# thtV1_0.net
KiCad netlist of a schematic drawn in EAGLE
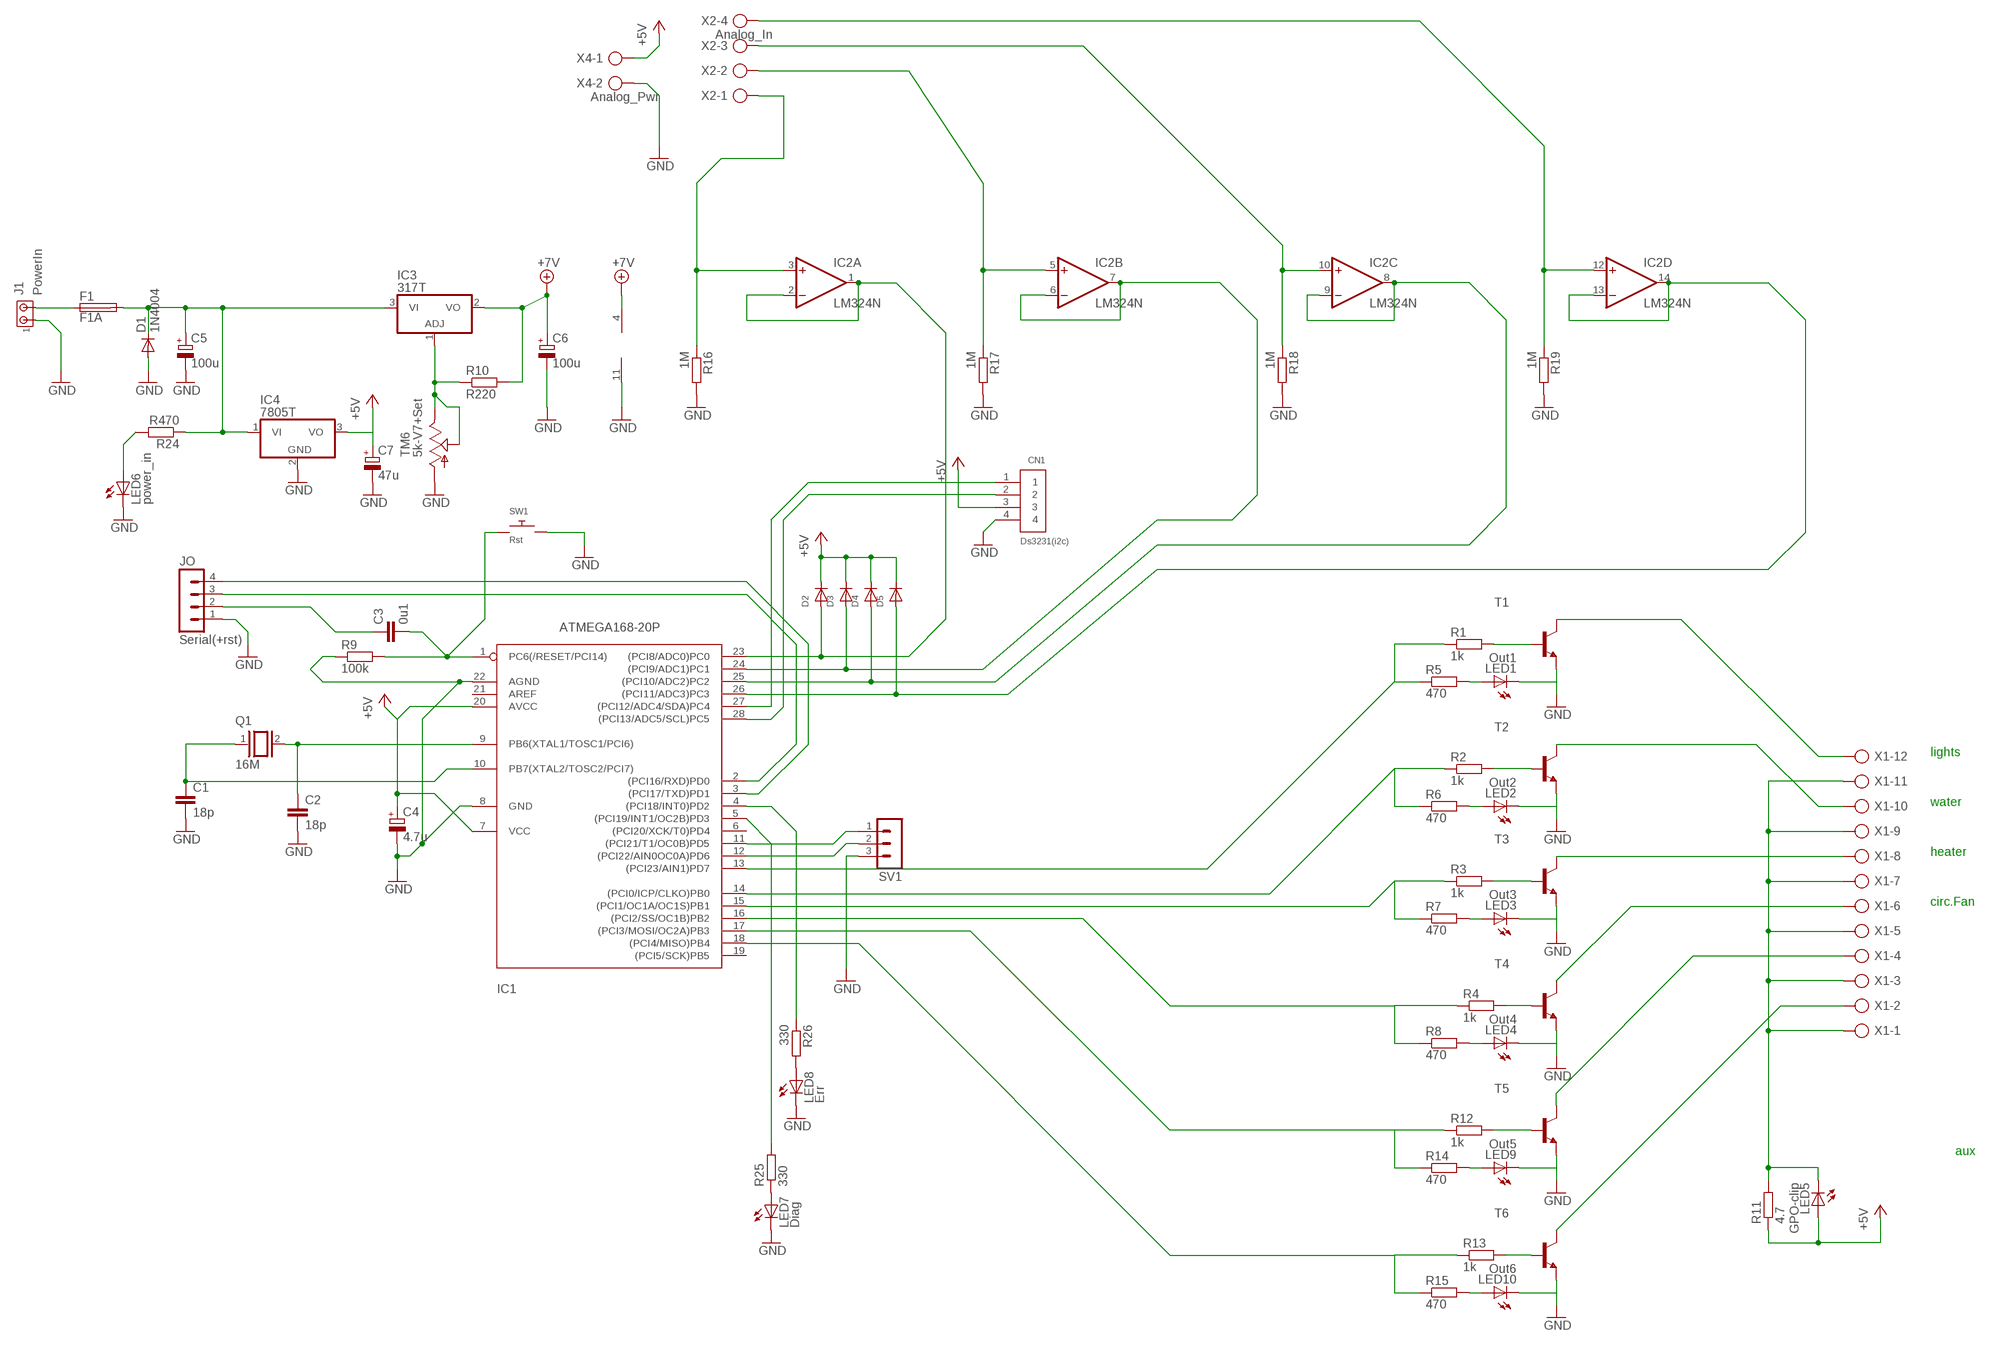
[diagram p0: schematic, sheet 1]

(export (version "E")
  (design (tool "Eeschema 10.0.6"))
  (components
    (comp (ref "C1")
      (value "18p")
      (footprint "eagle-import:C025-024X044")
      (libsource (lib "eagle-import") (part "C-EU025-024X044"))
    )
    (comp (ref "C2")
      (value "18p")
      (footprint "eagle-import:C025-024X044")
      (libsource (lib "eagle-import") (part "C-EU025-024X044"))
    )
    (comp (ref "C3")
      (value "0u1")
      (footprint "eagle-import:C050-030X075")
      (libsource (lib "eagle-import") (part "C-EU050-030X075"))
    )
    (comp (ref "C4")
      (value "4.7u")
      (footprint "eagle-import:E5-10,5")
      (libsource (lib "eagle-import") (part "CPOL-EUE5-10.5"))
    )
    (comp (ref "C5")
      (value "100u")
      (footprint "eagle-import:E5-10,5")
      (libsource (lib "eagle-import") (part "CPOL-EUE5-10.5"))
    )
    (comp (ref "C6")
      (value "100u")
      (footprint "eagle-import:E3,5-8")
      (libsource (lib "eagle-import") (part "CPOL-EUE3.5-8"))
    )
    (comp (ref "C7")
      (value "47u")
      (footprint "eagle-import:E2,5-6E")
      (libsource (lib "eagle-import") (part "CPOL-EUE2,5-6E"))
    )
    (comp (ref "CN1")
      (value "Ds3231(i2c)")
      (footprint "eagle-import:1X04-BIG")
      (libsource (lib "eagle-import") (part "1X4-BIG"))
    )
    (comp (ref "D1")
      (value "1N4004")
      (footprint "eagle-import:DO41-10")
      (libsource (lib "eagle-import") (part "1N4004"))
    )
    (comp (ref "D2")
      (value "DIODEDO-1N4148")
      (footprint "eagle-import:DO-1N4148")
      (libsource (lib "eagle-import") (part "DIODEDO-1N4148"))
    )
    (comp (ref "D3")
      (value "DIODEDO-1N4148")
      (footprint "eagle-import:DO-1N4148")
      (libsource (lib "eagle-import") (part "DIODEDO-1N4148"))
    )
    (comp (ref "D4")
      (value "DIODEDO-1N4148")
      (footprint "eagle-import:DO-1N4148")
      (libsource (lib "eagle-import") (part "DIODEDO-1N4148"))
    )
    (comp (ref "D5")
      (value "DIODEDO-1N4148")
      (footprint "eagle-import:DO-1N4148")
      (libsource (lib "eagle-import") (part "DIODEDO-1N4148"))
    )
    (comp (ref "F1")
      (value "F1A")
      (footprint "eagle-import:GSH15")
      (fields (field (name "MPN") "64900001039"))
      (libsource (lib "eagle-import") (part "GSH15"))
    )
    (comp (ref "IC1")
      (value "ATMEGA168-20P")
      (footprint "eagle-import:DIL28-3")
      (libsource (lib "eagle-import") (part "ATMEGA168P-20"))
    )
    (comp (ref "IC2")
      (value "LM324N")
      (footprint "eagle-import:DIL14")
      (libsource (lib "eagle-import") (part "LM324N"))
    )
    (comp (ref "IC3")
      (value "317T")
      (footprint "eagle-import:TO220H")
      (libsource (lib "eagle-import") (part "317T"))
    )
    (comp (ref "IC4")
      (value "7805T")
      (footprint "eagle-import:TO220H")
      (libsource (lib "eagle-import") (part "78T05"))
    )
    (comp (ref "J1")
      (value "PowerIn")
      (footprint "eagle-import:1X2MTA")
      (libsource (lib "eagle-import") (part "MTA02-156"))
    )
    (comp (ref "JO")
      (value "Serial(+rst)")
      (footprint "eagle-import:MA04-1")
      (libsource (lib "eagle-import") (part "MA04-1"))
    )
    (comp (ref "LED1")
      (value "Out1")
      (footprint "eagle-import:LED3MM")
      (libsource (lib "eagle-import") (part "LED3MM"))
    )
    (comp (ref "LED2")
      (value "Out2")
      (footprint "eagle-import:LED3MM")
      (libsource (lib "eagle-import") (part "LED3MM"))
    )
    (comp (ref "LED3")
      (value "Out3")
      (footprint "eagle-import:LED3MM")
      (libsource (lib "eagle-import") (part "LED3MM"))
    )
    (comp (ref "LED4")
      (value "Out4")
      (footprint "eagle-import:LED3MM")
      (libsource (lib "eagle-import") (part "LED3MM"))
    )
    (comp (ref "LED5")
      (value "GPO-clip")
      (footprint "eagle-import:LED3MM")
      (libsource (lib "eagle-import") (part "LED3MM"))
    )
    (comp (ref "LED6")
      (value "power_in")
      (footprint "eagle-import:LED3MM")
      (libsource (lib "eagle-import") (part "LED3MM"))
    )
    (comp (ref "LED7")
      (value "Diag")
      (footprint "eagle-import:LED3MM")
      (libsource (lib "eagle-import") (part "LED3MM"))
    )
    (comp (ref "LED8")
      (value "Err")
      (footprint "eagle-import:LED3MM")
      (libsource (lib "eagle-import") (part "LED3MM"))
    )
    (comp (ref "LED9")
      (value "Out5")
      (footprint "eagle-import:LED3MM")
      (libsource (lib "eagle-import") (part "LED3MM"))
    )
    (comp (ref "LED10")
      (value "Out6")
      (footprint "eagle-import:LED3MM")
      (libsource (lib "eagle-import") (part "LED3MM"))
    )
    (comp (ref "Q1")
      (value "16M")
      (footprint "eagle-import:QS")
      (libsource (lib "eagle-import") (part "XTAL/S"))
    )
    (comp (ref "R1")
      (value "1k")
      (footprint "eagle-import:0207_10")
      (libsource (lib "eagle-import") (part "R-EU_0207/10"))
    )
    (comp (ref "R2")
      (value "1k")
      (footprint "eagle-import:0207_10")
      (libsource (lib "eagle-import") (part "R-EU_0207/10"))
    )
    (comp (ref "R3")
      (value "1k")
      (footprint "eagle-import:0207_10")
      (libsource (lib "eagle-import") (part "R-EU_0207/10"))
    )
    (comp (ref "R4")
      (value "1k")
      (footprint "eagle-import:0207_10")
      (libsource (lib "eagle-import") (part "R-EU_0207/10"))
    )
    (comp (ref "R5")
      (value "470")
      (footprint "eagle-import:0204V")
      (libsource (lib "eagle-import") (part "R-EU_0204/2V"))
    )
    (comp (ref "R6")
      (value "470")
      (footprint "eagle-import:0204V")
      (libsource (lib "eagle-import") (part "R-EU_0204/2V"))
    )
    (comp (ref "R7")
      (value "470")
      (footprint "eagle-import:0204V")
      (libsource (lib "eagle-import") (part "R-EU_0204/2V"))
    )
    (comp (ref "R8")
      (value "470")
      (footprint "eagle-import:0204V")
      (libsource (lib "eagle-import") (part "R-EU_0204/2V"))
    )
    (comp (ref "R9")
      (value "100k")
      (footprint "eagle-import:0207_10")
      (libsource (lib "eagle-import") (part "R-EU_0207/10"))
    )
    (comp (ref "R10")
      (value "R220")
      (footprint "eagle-import:0207_10")
      (libsource (lib "eagle-import") (part "R-EU_0207/10"))
    )
    (comp (ref "R11")
      (value "4.7")
      (footprint "eagle-import:0207_10")
      (libsource (lib "eagle-import") (part "R-EU_0207/10"))
    )
    (comp (ref "R12")
      (value "1k")
      (footprint "eagle-import:0207_10")
      (libsource (lib "eagle-import") (part "R-EU_0207/10"))
    )
    (comp (ref "R13")
      (value "1k")
      (footprint "eagle-import:0207_10")
      (libsource (lib "eagle-import") (part "R-EU_0207/10"))
    )
    (comp (ref "R14")
      (value "470")
      (footprint "eagle-import:0204V")
      (libsource (lib "eagle-import") (part "R-EU_0204/2V"))
    )
    (comp (ref "R15")
      (value "470")
      (footprint "eagle-import:0204V")
      (libsource (lib "eagle-import") (part "R-EU_0204/2V"))
    )
    (comp (ref "R16")
      (value "1M")
      (footprint "eagle-import:0204V")
      (libsource (lib "eagle-import") (part "R-EU_0204/2V"))
    )
    (comp (ref "R17")
      (value "1M")
      (footprint "eagle-import:0204V")
      (libsource (lib "eagle-import") (part "R-EU_0204/2V"))
    )
    (comp (ref "R18")
      (value "1M")
      (footprint "eagle-import:0204V")
      (libsource (lib "eagle-import") (part "R-EU_0204/2V"))
    )
    (comp (ref "R19")
      (value "1M")
      (footprint "eagle-import:0204V")
      (libsource (lib "eagle-import") (part "R-EU_0204/2V"))
    )
    (comp (ref "R24")
      (value "R470")
      (footprint "eagle-import:0207_10")
      (libsource (lib "eagle-import") (part "R-EU_0207/10"))
    )
    (comp (ref "R25")
      (value "330")
      (footprint "eagle-import:0207_2V")
      (libsource (lib "eagle-import") (part "R-EU_0207/2V"))
    )
    (comp (ref "R26")
      (value "330")
      (footprint "eagle-import:0207_2V")
      (libsource (lib "eagle-import") (part "R-EU_0207/2V"))
    )
    (comp (ref "SV1")
      (value "MA03-1")
      (footprint "eagle-import:MA03-1")
      (libsource (lib "eagle-import") (part "MA03-1"))
    )
    (comp (ref "SW1")
      (value "Rst")
      (footprint "eagle-import:TACT_PANA-EVQ")
      (libsource (lib "eagle-import") (part "SWITCH_PUSHBUTTONEVQ-PE"))
    )
    (comp (ref "T1")
      (value "BC547A-NPN-TO92-CBE")
      (footprint "eagle-import:TO92-CBE")
      (libsource (lib "eagle-import") (part "-NPN-TO92-CBEBC547A"))
    )
    (comp (ref "T2")
      (value "BC547A-NPN-TO92-CBE")
      (footprint "eagle-import:TO92-CBE")
      (libsource (lib "eagle-import") (part "-NPN-TO92-CBEBC547A"))
    )
    (comp (ref "T3")
      (value "BC547A-NPN-TO92-CBE")
      (footprint "eagle-import:TO92-CBE")
      (libsource (lib "eagle-import") (part "-NPN-TO92-CBEBC547A"))
    )
    (comp (ref "T4")
      (value "BC547A-NPN-TO92-CBE")
      (footprint "eagle-import:TO92-CBE")
      (libsource (lib "eagle-import") (part "-NPN-TO92-CBEBC547A"))
    )
    (comp (ref "T5")
      (value "BC547A-NPN-TO92-CBE")
      (footprint "eagle-import:TO92-CBE")
      (libsource (lib "eagle-import") (part "-NPN-TO92-CBEBC547A"))
    )
    (comp (ref "T6")
      (value "BC547A-NPN-TO92-CBE")
      (footprint "eagle-import:TO92-CBE")
      (libsource (lib "eagle-import") (part "-NPN-TO92-CBEBC547A"))
    )
    (comp (ref "TM6")
      (value "5k-V7+Set")
      (footprint "eagle-import:6MM")
      (libsource (lib "eagle-import") (part "TRIM"))
    )
    (comp (ref "X1")
      (value "AK300/12")
      (footprint "eagle-import:AK300_12")
      (libsource (lib "eagle-import") (part "AK300/12"))
    )
    (comp (ref "X2")
      (value "Analog_In")
      (footprint "eagle-import:AK300_4")
      (libsource (lib "eagle-import") (part "AK300/4"))
    )
    (comp (ref "X4")
      (value "Analog_Pwr")
      (footprint "eagle-import:AK300_2")
      (libsource (lib "eagle-import") (part "AK300/2"))
    )
  )
  (nets
    (net (code "1") (name "+5V") (class "Default")
      (node (ref "C4") (pin "+") (pinfunction "+_+") (pintype "passive"))
      (node (ref "C7") (pin "+") (pinfunction "+_+") (pintype "passive"))
      (node (ref "CN1") (pin "3") (pinfunction "3_3") (pintype "bidirectional"))
      (node (ref "D2") (pin "C") (pinfunction "C_C") (pintype "passive"))
      (node (ref "D3") (pin "C") (pinfunction "C_C") (pintype "passive"))
      (node (ref "D4") (pin "C") (pinfunction "C_C") (pintype "passive"))
      (node (ref "D5") (pin "C") (pinfunction "C_C") (pintype "passive"))
      (node (ref "IC1") (pin "20") (pinfunction "AVCC_20") (pintype "bidirectional"))
      (node (ref "IC1") (pin "7") (pinfunction "VCC_7") (pintype "bidirectional"))
      (node (ref "IC4") (pin "3") (pinfunction "VO_3") (pintype "passive"))
      (node (ref "LED5") (pin "A") (pinfunction "A_A") (pintype "passive"))
      (node (ref "R11") (pin "1") (pinfunction "1_1") (pintype "passive"))
      (node (ref "X4") (pin "1") (pinfunction "KL_1") (pintype "passive"))
    )
    (net (code "2") (name "+7V") (class "Default")
      (node (ref "C6") (pin "+") (pinfunction "+_+") (pintype "passive"))
      (node (ref "IC2") (pin "4") (pinfunction "V+_4") (pintype "power_in"))
      (node (ref "IC3") (pin "2") (pinfunction "VO_2") (pintype "passive"))
      (node (ref "R10") (pin "2") (pinfunction "2_2") (pintype "passive"))
    )
    (net (code "3") (name "GND") (class "Default")
      (node (ref "C1") (pin "2") (pinfunction "2_2") (pintype "passive"))
      (node (ref "C2") (pin "2") (pinfunction "2_2") (pintype "passive"))
      (node (ref "C4") (pin "-") (pinfunction "-_-") (pintype "passive"))
      (node (ref "C5") (pin "-") (pinfunction "-_-") (pintype "passive"))
      (node (ref "C6") (pin "-") (pinfunction "-_-") (pintype "passive"))
      (node (ref "C7") (pin "-") (pinfunction "-_-") (pintype "passive"))
      (node (ref "CN1") (pin "4") (pinfunction "4_4") (pintype "bidirectional"))
      (node (ref "D1") (pin "A") (pinfunction "A_A") (pintype "passive"))
      (node (ref "IC1") (pin "22") (pinfunction "AGND_22") (pintype "bidirectional"))
      (node (ref "IC1") (pin "8") (pinfunction "GND_8") (pintype "bidirectional"))
      (node (ref "IC2") (pin "11") (pinfunction "V-_11") (pintype "power_in"))
      (node (ref "IC4") (pin "2") (pinfunction "GND_2") (pintype "passive"))
      (node (ref "J1") (pin "1") (pinfunction "1_1") (pintype "passive"))
      (node (ref "JO") (pin "1") (pinfunction "1_1") (pintype "passive"))
      (node (ref "LED1") (pin "K") (pinfunction "C_K") (pintype "passive"))
      (node (ref "LED10") (pin "K") (pinfunction "C_K") (pintype "passive"))
      (node (ref "LED2") (pin "K") (pinfunction "C_K") (pintype "passive"))
      (node (ref "LED3") (pin "K") (pinfunction "C_K") (pintype "passive"))
      (node (ref "LED4") (pin "K") (pinfunction "C_K") (pintype "passive"))
      (node (ref "LED6") (pin "K") (pinfunction "C_K") (pintype "passive"))
      (node (ref "LED7") (pin "K") (pinfunction "C_K") (pintype "passive"))
      (node (ref "LED8") (pin "K") (pinfunction "C_K") (pintype "passive"))
      (node (ref "LED9") (pin "K") (pinfunction "C_K") (pintype "passive"))
      (node (ref "R16") (pin "2") (pinfunction "2_2") (pintype "passive"))
      (node (ref "R17") (pin "2") (pinfunction "2_2") (pintype "passive"))
      (node (ref "R18") (pin "2") (pinfunction "2_2") (pintype "passive"))
      (node (ref "R19") (pin "2") (pinfunction "2_2") (pintype "passive"))
      (node (ref "R9") (pin "1") (pinfunction "1_1") (pintype "passive"))
      (node (ref "SV1") (pin "3") (pinfunction "3_3") (pintype "passive"))
      (node (ref "SW1") (pin "P$2") (pinfunction "P$2_P$2") (pintype "passive"))
      (node (ref "T1") (pin "E") (pinfunction "E_E") (pintype "passive"))
      (node (ref "T2") (pin "E") (pinfunction "E_E") (pintype "passive"))
      (node (ref "T3") (pin "E") (pinfunction "E_E") (pintype "passive"))
      (node (ref "T4") (pin "E") (pinfunction "E_E") (pintype "passive"))
      (node (ref "T5") (pin "E") (pinfunction "E_E") (pintype "passive"))
      (node (ref "T6") (pin "E") (pinfunction "E_E") (pintype "passive"))
      (node (ref "TM6") (pin "A") (pinfunction "A_A") (pintype "passive"))
      (node (ref "X4") (pin "2") (pinfunction "KL_2") (pintype "passive"))
    )
    (net (code "4") (name "Net-(C3-Pad1)") (class "Default")
      (node (ref "C3") (pin "1") (pinfunction "1_1") (pintype "passive"))
      (node (ref "JO") (pin "2") (pinfunction "2_2") (pintype "passive"))
    )
    (net (code "5") (name "Net-(F1-Pad1)") (class "Default")
      (node (ref "F1") (pin "1") (pinfunction "1_1") (pintype "passive"))
      (node (ref "J1") (pin "2") (pinfunction "2_2") (pintype "passive"))
    )
    (net (code "6") (name "Net-(IC1-(PCI0{slash}ICP{slash}CLKO)PB0)") (class "Default")
      (node (ref "IC1") (pin "14") (pinfunction "(PCI0/ICP/CLKO)PB0_14") (pintype "bidirectional"))
      (node (ref "R2") (pin "1") (pinfunction "1_1") (pintype "passive"))
      (node (ref "R6") (pin "1") (pinfunction "1_1") (pintype "passive"))
    )
    (net (code "7") (name "Net-(IC1-(PCI1{slash}OC1A{slash}OC1S)PB1)") (class "Default")
      (node (ref "IC1") (pin "15") (pinfunction "(PCI1/OC1A/OC1S)PB1_15") (pintype "bidirectional"))
      (node (ref "R3") (pin "1") (pinfunction "1_1") (pintype "passive"))
      (node (ref "R7") (pin "1") (pinfunction "1_1") (pintype "passive"))
    )
    (net (code "8") (name "Net-(IC1-(PCI2{slash}SS{slash}OC1B)PB2)") (class "Default")
      (node (ref "IC1") (pin "16") (pinfunction "(PCI2/SS/OC1B)PB2_16") (pintype "bidirectional"))
      (node (ref "R4") (pin "1") (pinfunction "1_1") (pintype "passive"))
      (node (ref "R8") (pin "1") (pinfunction "1_1") (pintype "passive"))
    )
    (net (code "9") (name "Net-(IC1-(PCI3{slash}MOSI{slash}OC2A)PB3)") (class "Default")
      (node (ref "IC1") (pin "17") (pinfunction "(PCI3/MOSI/OC2A)PB3_17") (pintype "bidirectional"))
      (node (ref "R12") (pin "1") (pinfunction "1_1") (pintype "passive"))
      (node (ref "R14") (pin "1") (pinfunction "1_1") (pintype "passive"))
    )
    (net (code "10") (name "Net-(IC1-(PCI4{slash}MISO)PB4)") (class "Default")
      (node (ref "IC1") (pin "18") (pinfunction "(PCI4/MISO)PB4_18") (pintype "bidirectional"))
      (node (ref "R13") (pin "1") (pinfunction "1_1") (pintype "passive"))
      (node (ref "R15") (pin "1") (pinfunction "1_1") (pintype "passive"))
    )
    (net (code "11") (name "Net-(IC1-(PCI8{slash}ADC0)PC0)") (class "Default")
      (node (ref "D2") (pin "A") (pinfunction "A_A") (pintype "passive"))
      (node (ref "IC1") (pin "23") (pinfunction "(PCI8/ADC0)PC0_23") (pintype "bidirectional"))
      (node (ref "IC2") (pin "1") (pinfunction "OUT_1") (pintype "output"))
      (node (ref "IC2") (pin "2") (pinfunction "-IN_2") (pintype "input"))
    )
    (net (code "12") (name "Net-(IC1-(PCI9{slash}ADC1)PC1)") (class "Default")
      (node (ref "D3") (pin "A") (pinfunction "A_A") (pintype "passive"))
      (node (ref "IC1") (pin "24") (pinfunction "(PCI9/ADC1)PC1_24") (pintype "bidirectional"))
      (node (ref "IC2") (pin "6") (pinfunction "-IN_6") (pintype "input"))
      (node (ref "IC2") (pin "7") (pinfunction "OUT_7") (pintype "output"))
    )
    (net (code "13") (name "Net-(IC1-(PCI10{slash}ADC2)PC2)") (class "Default")
      (node (ref "D4") (pin "A") (pinfunction "A_A") (pintype "passive"))
      (node (ref "IC1") (pin "25") (pinfunction "(PCI10/ADC2)PC2_25") (pintype "bidirectional"))
      (node (ref "IC2") (pin "8") (pinfunction "OUT_8") (pintype "output"))
      (node (ref "IC2") (pin "9") (pinfunction "-IN_9") (pintype "input"))
    )
    (net (code "14") (name "Net-(IC1-(PCI11{slash}ADC3)PC3)") (class "Default")
      (node (ref "D5") (pin "A") (pinfunction "A_A") (pintype "passive"))
      (node (ref "IC1") (pin "26") (pinfunction "(PCI11/ADC3)PC3_26") (pintype "bidirectional"))
      (node (ref "IC2") (pin "13") (pinfunction "-IN_13") (pintype "input"))
      (node (ref "IC2") (pin "14") (pinfunction "OUT_14") (pintype "output"))
    )
    (net (code "15") (name "Net-(IC1-(PCI12{slash}ADC4{slash}SDA)PC4)") (class "Default")
      (node (ref "CN1") (pin "1") (pinfunction "1_1") (pintype "bidirectional"))
      (node (ref "IC1") (pin "27") (pinfunction "(PCI12/ADC4/SDA)PC4_27") (pintype "bidirectional"))
    )
    (net (code "16") (name "Net-(IC1-(PCI13{slash}ADC5{slash}SCL)PC5)") (class "Default")
      (node (ref "CN1") (pin "2") (pinfunction "2_2") (pintype "bidirectional"))
      (node (ref "IC1") (pin "28") (pinfunction "(PCI13/ADC5/SCL)PC5_28") (pintype "bidirectional"))
    )
    (net (code "17") (name "Net-(IC1-(PCI16{slash}RXD)PD0)") (class "Default")
      (node (ref "IC1") (pin "2") (pinfunction "(PCI16/RXD)PD0_2") (pintype "bidirectional"))
      (node (ref "JO") (pin "3") (pinfunction "3_3") (pintype "passive"))
    )
    (net (code "18") (name "Net-(IC1-(PCI17{slash}TXD)PD1)") (class "Default")
      (node (ref "IC1") (pin "3") (pinfunction "(PCI17/TXD)PD1_3") (pintype "bidirectional"))
      (node (ref "JO") (pin "4") (pinfunction "4_4") (pintype "passive"))
    )
    (net (code "19") (name "Net-(IC1-(PCI18{slash}INT0)PD2)") (class "Default")
      (node (ref "IC1") (pin "4") (pinfunction "(PCI18/INT0)PD2_4") (pintype "bidirectional"))
      (node (ref "R26") (pin "1") (pinfunction "1_1") (pintype "passive"))
    )
    (net (code "20") (name "Net-(IC1-(PCI19{slash}INT1{slash}OC2B)PD3)") (class "Default")
      (node (ref "IC1") (pin "5") (pinfunction "(PCI19/INT1/OC2B)PD3_5") (pintype "bidirectional"))
      (node (ref "R25") (pin "2") (pinfunction "2_2") (pintype "passive"))
    )
    (net (code "21") (name "Net-(IC1-(PCI21{slash}T1{slash}OC0B)PD5)") (class "Default")
      (node (ref "IC1") (pin "11") (pinfunction "(PCI21/T1/OC0B)PD5_11") (pintype "bidirectional"))
      (node (ref "SV1") (pin "1") (pinfunction "1_1") (pintype "passive"))
    )
    (net (code "22") (name "Net-(IC1-(PCI22{slash}AIN0OC0A)PD6)") (class "Default")
      (node (ref "IC1") (pin "12") (pinfunction "(PCI22/AIN0OC0A)PD6_12") (pintype "bidirectional"))
      (node (ref "SV1") (pin "2") (pinfunction "2_2") (pintype "passive"))
    )
    (net (code "23") (name "Net-(IC1-(PCI23{slash}AIN1)PD7)") (class "Default")
      (node (ref "IC1") (pin "13") (pinfunction "(PCI23/AIN1)PD7_13") (pintype "bidirectional"))
      (node (ref "R1") (pin "1") (pinfunction "1_1") (pintype "passive"))
      (node (ref "R5") (pin "1") (pinfunction "1_1") (pintype "passive"))
    )
    (net (code "24") (name "Net-(IC1-PB6(XTAL1{slash}TOSC1{slash}PCI6))") (class "Default")
      (node (ref "C2") (pin "1") (pinfunction "1_1") (pintype "passive"))
      (node (ref "IC1") (pin "9") (pinfunction "PB6(XTAL1/TOSC1/PCI6)_9") (pintype "bidirectional"))
      (node (ref "Q1") (pin "2") (pinfunction "2_2") (pintype "passive"))
    )
    (net (code "25") (name "Net-(IC1-PB7(XTAL2{slash}TOSC2{slash}PCI7))") (class "Default")
      (node (ref "C1") (pin "1") (pinfunction "1_1") (pintype "passive"))
      (node (ref "IC1") (pin "10") (pinfunction "PB7(XTAL2/TOSC2/PCI7)_10") (pintype "bidirectional"))
      (node (ref "Q1") (pin "1") (pinfunction "1_1") (pintype "passive"))
    )
    (net (code "26") (name "Net-(IC1-PC6({slash}RESET{slash}PCI14))") (class "Default")
      (node (ref "C3") (pin "2") (pinfunction "2_2") (pintype "passive"))
      (node (ref "IC1") (pin "1") (pinfunction "PC6(/RESET/PCI14)_1") (pintype "bidirectional"))
      (node (ref "R9") (pin "2") (pinfunction "2_2") (pintype "passive"))
      (node (ref "SW1") (pin "P$1") (pinfunction "P$1_P$1") (pintype "passive"))
    )
    (net (code "27") (name "Net-(IC2A-+IN)") (class "Default")
      (node (ref "IC2") (pin "3") (pinfunction "+IN_3") (pintype "input"))
      (node (ref "R16") (pin "1") (pinfunction "1_1") (pintype "passive"))
      (node (ref "X2") (pin "1") (pinfunction "KL_1") (pintype "passive"))
    )
    (net (code "28") (name "Net-(IC2B-+IN)") (class "Default")
      (node (ref "IC2") (pin "5") (pinfunction "+IN_5") (pintype "input"))
      (node (ref "R17") (pin "1") (pinfunction "1_1") (pintype "passive"))
      (node (ref "X2") (pin "2") (pinfunction "KL_2") (pintype "passive"))
    )
    (net (code "29") (name "Net-(IC2C-+IN)") (class "Default")
      (node (ref "IC2") (pin "10") (pinfunction "+IN_10") (pintype "input"))
      (node (ref "R18") (pin "1") (pinfunction "1_1") (pintype "passive"))
      (node (ref "X2") (pin "3") (pinfunction "KL_3") (pintype "passive"))
    )
    (net (code "30") (name "Net-(IC2D-+IN)") (class "Default")
      (node (ref "IC2") (pin "12") (pinfunction "+IN_12") (pintype "input"))
      (node (ref "R19") (pin "1") (pinfunction "1_1") (pintype "passive"))
      (node (ref "X2") (pin "4") (pinfunction "KL_4") (pintype "passive"))
    )
    (net (code "31") (name "Net-(IC3-ADJ)") (class "Default")
      (node (ref "IC3") (pin "1") (pinfunction "ADJ_1") (pintype "input"))
      (node (ref "R10") (pin "1") (pinfunction "1_1") (pintype "passive"))
      (node (ref "TM6") (pin "E") (pinfunction "E_E") (pintype "passive"))
      (node (ref "TM6") (pin "S") (pinfunction "S_S") (pintype "passive"))
    )
    (net (code "32") (name "Net-(IC3-VI)") (class "Default")
      (node (ref "C5") (pin "+") (pinfunction "+_+") (pintype "passive"))
      (node (ref "D1") (pin "C") (pinfunction "C_C") (pintype "passive"))
      (node (ref "F1") (pin "2") (pinfunction "2_2") (pintype "passive"))
      (node (ref "IC3") (pin "3") (pinfunction "VI_3") (pintype "input"))
      (node (ref "IC4") (pin "1") (pinfunction "VI_1") (pintype "input"))
      (node (ref "R24") (pin "1") (pinfunction "1_1") (pintype "passive"))
    )
    (net (code "33") (name "Net-(LED1-PadA)") (class "Default")
      (node (ref "LED1") (pin "A") (pinfunction "A_A") (pintype "passive"))
      (node (ref "R5") (pin "2") (pinfunction "2_2") (pintype "passive"))
    )
    (net (code "34") (name "Net-(LED2-PadA)") (class "Default")
      (node (ref "LED2") (pin "A") (pinfunction "A_A") (pintype "passive"))
      (node (ref "R6") (pin "2") (pinfunction "2_2") (pintype "passive"))
    )
    (net (code "35") (name "Net-(LED3-PadA)") (class "Default")
      (node (ref "LED3") (pin "A") (pinfunction "A_A") (pintype "passive"))
      (node (ref "R7") (pin "2") (pinfunction "2_2") (pintype "passive"))
    )
    (net (code "36") (name "Net-(LED4-PadA)") (class "Default")
      (node (ref "LED4") (pin "A") (pinfunction "A_A") (pintype "passive"))
      (node (ref "R8") (pin "2") (pinfunction "2_2") (pintype "passive"))
    )
    (net (code "37") (name "Net-(LED5-C)") (class "Default")
      (node (ref "LED5") (pin "K") (pinfunction "C_K") (pintype "passive"))
      (node (ref "R11") (pin "2") (pinfunction "2_2") (pintype "passive"))
      (node (ref "X1") (pin "1") (pinfunction "KL_1") (pintype "passive"))
      (node (ref "X1") (pin "11") (pinfunction "KL_11") (pintype "passive"))
      (node (ref "X1") (pin "3") (pinfunction "KL_3") (pintype "passive"))
      (node (ref "X1") (pin "5") (pinfunction "KL_5") (pintype "passive"))
      (node (ref "X1") (pin "7") (pinfunction "KL_7") (pintype "passive"))
      (node (ref "X1") (pin "9") (pinfunction "KL_9") (pintype "passive"))
    )
    (net (code "38") (name "Net-(LED6-PadA)") (class "Default")
      (node (ref "LED6") (pin "A") (pinfunction "A_A") (pintype "passive"))
      (node (ref "R24") (pin "2") (pinfunction "2_2") (pintype "passive"))
    )
    (net (code "39") (name "Net-(LED7-PadA)") (class "Default")
      (node (ref "LED7") (pin "A") (pinfunction "A_A") (pintype "passive"))
      (node (ref "R25") (pin "1") (pinfunction "1_1") (pintype "passive"))
    )
    (net (code "40") (name "Net-(LED8-PadA)") (class "Default")
      (node (ref "LED8") (pin "A") (pinfunction "A_A") (pintype "passive"))
      (node (ref "R26") (pin "2") (pinfunction "2_2") (pintype "passive"))
    )
    (net (code "41") (name "Net-(LED9-PadA)") (class "Default")
      (node (ref "LED9") (pin "A") (pinfunction "A_A") (pintype "passive"))
      (node (ref "R14") (pin "2") (pinfunction "2_2") (pintype "passive"))
    )
    (net (code "42") (name "Net-(LED10-PadA)") (class "Default")
      (node (ref "LED10") (pin "A") (pinfunction "A_A") (pintype "passive"))
      (node (ref "R15") (pin "2") (pinfunction "2_2") (pintype "passive"))
    )
    (net (code "43") (name "Net-(R1-Pad2)") (class "Default")
      (node (ref "R1") (pin "2") (pinfunction "2_2") (pintype "passive"))
      (node (ref "T1") (pin "B") (pinfunction "B_B") (pintype "passive"))
    )
    (net (code "44") (name "Net-(R2-Pad2)") (class "Default")
      (node (ref "R2") (pin "2") (pinfunction "2_2") (pintype "passive"))
      (node (ref "T2") (pin "B") (pinfunction "B_B") (pintype "passive"))
    )
    (net (code "45") (name "Net-(R3-Pad2)") (class "Default")
      (node (ref "R3") (pin "2") (pinfunction "2_2") (pintype "passive"))
      (node (ref "T3") (pin "B") (pinfunction "B_B") (pintype "passive"))
    )
    (net (code "46") (name "Net-(R4-Pad2)") (class "Default")
      (node (ref "R4") (pin "2") (pinfunction "2_2") (pintype "passive"))
      (node (ref "T4") (pin "B") (pinfunction "B_B") (pintype "passive"))
    )
    (net (code "47") (name "Net-(R12-Pad2)") (class "Default")
      (node (ref "R12") (pin "2") (pinfunction "2_2") (pintype "passive"))
      (node (ref "T5") (pin "B") (pinfunction "B_B") (pintype "passive"))
    )
    (net (code "48") (name "Net-(R13-Pad2)") (class "Default")
      (node (ref "R13") (pin "2") (pinfunction "2_2") (pintype "passive"))
      (node (ref "T6") (pin "B") (pinfunction "B_B") (pintype "passive"))
    )
    (net (code "49") (name "Net-(X1B-KL)") (class "Default")
      (node (ref "T2") (pin "C") (pinfunction "C_C") (pintype "passive"))
      (node (ref "X1") (pin "10") (pinfunction "KL_10") (pintype "passive"))
    )
    (net (code "50") (name "Net-(X1D-KL)") (class "Default")
      (node (ref "T1") (pin "C") (pinfunction "C_C") (pintype "passive"))
      (node (ref "X1") (pin "12") (pinfunction "KL_12") (pintype "passive"))
    )
    (net (code "51") (name "Net-(X1E-KL)") (class "Default")
      (node (ref "T6") (pin "C") (pinfunction "C_C") (pintype "passive"))
      (node (ref "X1") (pin "2") (pinfunction "KL_2") (pintype "passive"))
    )
    (net (code "52") (name "Net-(X1G-KL)") (class "Default")
      (node (ref "T5") (pin "C") (pinfunction "C_C") (pintype "passive"))
      (node (ref "X1") (pin "4") (pinfunction "KL_4") (pintype "passive"))
    )
    (net (code "53") (name "Net-(X1I-KL)") (class "Default")
      (node (ref "T4") (pin "C") (pinfunction "C_C") (pintype "passive"))
      (node (ref "X1") (pin "6") (pinfunction "KL_6") (pintype "passive"))
    )
    (net (code "54") (name "Net-(X1K-KL)") (class "Default")
      (node (ref "T3") (pin "C") (pinfunction "C_C") (pintype "passive"))
      (node (ref "X1") (pin "8") (pinfunction "KL_8") (pintype "passive"))
    )
    (net (code "55") (name "unconnected-(IC1-(PCI5{slash}SCK)PB5-Pad19)") (class "Default")
      (node (ref "IC1") (pin "19") (pinfunction "(PCI5/SCK)PB5_19") (pintype "bidirectional"))
    )
    (net (code "56") (name "unconnected-(IC1-(PCI20{slash}XCK{slash}T0)PD4-Pad6)") (class "Default")
      (node (ref "IC1") (pin "6") (pinfunction "(PCI20/XCK/T0)PD4_6") (pintype "bidirectional"))
    )
    (net (code "57") (name "unconnected-(IC1-AREF-Pad21)") (class "Default")
      (node (ref "IC1") (pin "21") (pinfunction "AREF_21") (pintype "bidirectional"))
    )
  )
)
